# RP5_Battery_Flex.net
KiCad netlist of a schematic drawn in Altium Designer
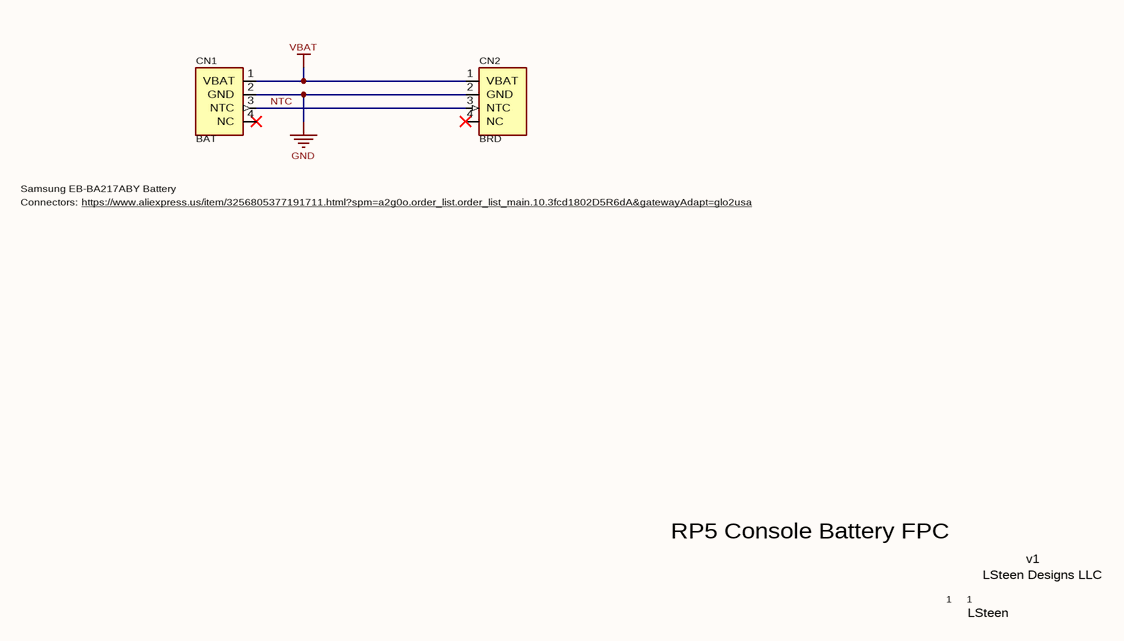
[diagram p0: RP5_Battery_Flex.SchDoc]

(export (version "E")
  (design (tool "Eeschema 10.0.6"))
  (components
    (comp (ref "CN1")
      (value "BAT")
      (footprint "BAT_SS_EB-BA217ABY")
      (description "Samsung battery connector")
      (libsource (lib "Schlib1") (part "BAT_SS_EB-BA217ABY"))
    )
    (comp (ref "CN2")
      (value "BRD")
      (footprint "BAT_SS_EB-BA217ABY_FLEX_CN")
      (description "Samsung battery connector")
      (libsource (lib "Schlib1") (part "BAT_SS_EB-BA217ABY_FLEX_CN"))
    )
  )
  (nets
    (net (code "1") (name "/NTC") (class "Default")
      (node (ref "CN1") (pin "3") (pinfunction "NTC_3") (pintype "output"))
      (node (ref "CN2") (pin "3") (pinfunction "NTC_3") (pintype "input"))
    )
    (net (code "2") (name "GND") (class "Default")
      (node (ref "CN1") (pin "2") (pinfunction "GND_2") (pintype "power_in"))
      (node (ref "CN2") (pin "2") (pinfunction "GND_2") (pintype "power_in"))
    )
    (net (code "3") (name "VBAT") (class "Default")
      (node (ref "CN1") (pin "1") (pinfunction "VBAT_1") (pintype "power_in"))
      (node (ref "CN2") (pin "1") (pinfunction "VBAT_1") (pintype "power_in"))
    )
    (net (code "4") (name "unconnected-(CN1-NC-Pad4)") (class "Default")
      (node (ref "CN1") (pin "4") (pinfunction "NC_4") (pintype "power_in+no_connect"))
    )
    (net (code "5") (name "unconnected-(CN2-NC-Pad4)") (class "Default")
      (node (ref "CN2") (pin "4") (pinfunction "NC_4") (pintype "power_in+no_connect"))
    )
  )
)
